# ON_OFF_Controller.net
KiCad netlist of a schematic drawn in Altium Designer
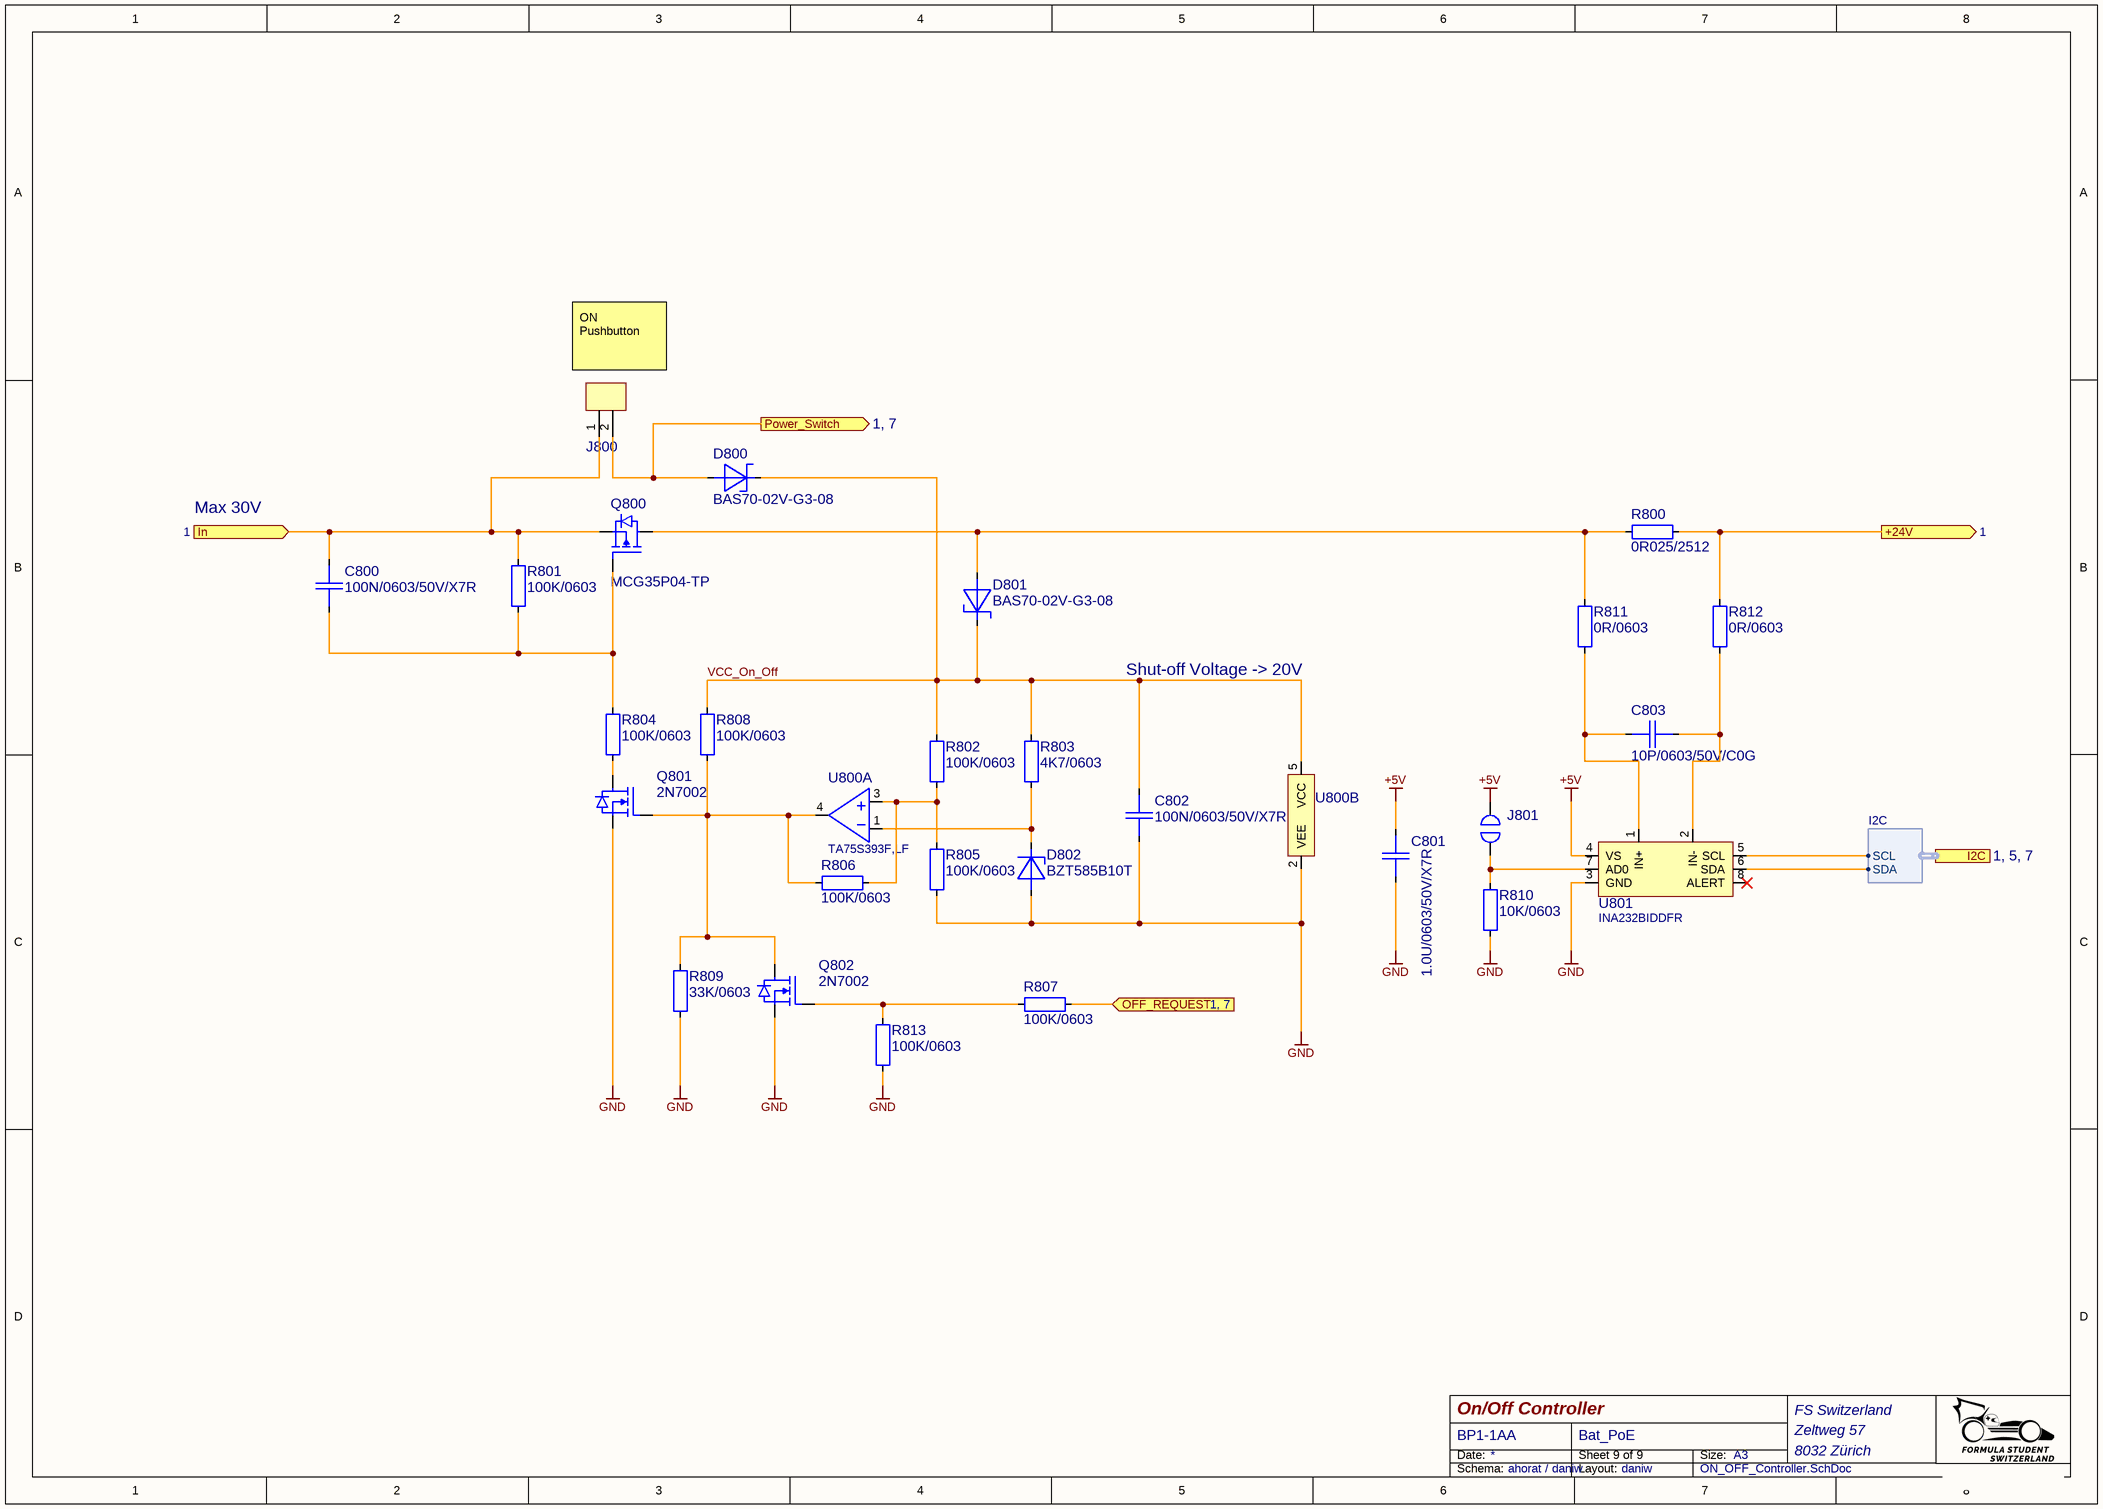
[diagram p0: ON_OFF_Controller.SchDoc]

(export (version "E")
  (design (tool "Eeschema 10.0.6"))
  (components
    (comp (ref "C800")
      (value "100N/0603/50V/X7R")
      (footprint "CAP0603_X7R")
      (description "CAP SM 0603 100nF 50V X7R")
      (fields (field (name "MANUFACTURER") "GENERIC"))
      (libsource (lib "daniw_altium_lib") (part "C"))
    )
    (comp (ref "C801")
      (value "1.0U/0603/50V/X7R")
      (footprint "CAP0603_X7R")
      (description "CAP SM 0603 1.0uF 50V X7R")
      (fields (field (name "MANUFACTURER") "GENERIC"))
      (libsource (lib "daniw_altium_lib") (part "C"))
    )
    (comp (ref "C802")
      (value "100N/0603/50V/X7R")
      (footprint "CAP0603_X7R")
      (description "CAP SM 0603 100nF 50V X7R")
      (fields (field (name "MANUFACTURER") "GENERIC"))
      (libsource (lib "daniw_altium_lib") (part "C"))
    )
    (comp (ref "C803")
      (value "10P/0603/50V/C0G")
      (footprint "CAP0603_C0G")
      (description "CAP SM 0603 10pF 50V C0G")
      (fields (field (name "MANUFACTURER") "GENERIC"))
      (libsource (lib "daniw_altium_lib") (part "C"))
    )
    (comp (ref "D800")
      (value "BAS70-02V-G3-08")
      (footprint "SOD1608X065")
      (description "Small Signal Schottky Diode")
      (fields (field (name "MANUFACTURER") "Vishay"))
      (libsource (lib "daniw_altium_lib") (part "D_Schottky"))
    )
    (comp (ref "D801")
      (value "BAS70-02V-G3-08")
      (footprint "SOD1608X065")
      (description "Small Signal Schottky Diode")
      (fields (field (name "MANUFACTURER") "Vishay"))
      (libsource (lib "daniw_altium_lib") (part "D_Schottky"))
    )
    (comp (ref "D802")
      (value "BZT585B10T")
      (footprint "SOD1608X065")
      (description "DIODE ZENER 10V 350MW SOD523")
      (fields (field (name "MANUFACTURER") "Diodes Incorporated"))
      (libsource (lib "daniw_altium_lib") (part "D_Zener"))
    )
    (comp (ref "J800")
      (value "5600200220")
      (footprint "5600200220")
      (description "DuraClik Wire-to-Board Header, Single Row, Vertical, 2 Circuits, Tin (Sn) Over Nickel, Natural")
      (fields (field (name "PART NUMBER") "DuraClick_1x2_VERT_SMD") (field (name "MANUFACTURER") "Molex"))
      (libsource (lib "daniw_altium_lib") (part "CON2"))
    )
    (comp (ref "J801")
      (value "Solder Jumper 2pin 0.2mm small")
      (footprint "Solder_Jumper_2pin_0.2mm_small")
      (description "Solder jumper with two pins with a spacing of 0.2mm")
      (fields
        (field (name "PART NUMBER") "Solder_Jumper_2pin_0.2mm_small")
        (field (name "MANUFACTURER") "NONE")
      )
      (libsource (lib "daniw_altium_lib") (part "SolderJumper_2"))
    )
    (comp (ref "Q800")
      (value "MCG35P04-TP")
      (footprint "SON065P330X330X075-5-TH245X175")
      (description "40V 35A P-Channel MOSFET")
      (fields (field (name "MANUFACTURER") "Micro Commercial Co"))
      (libsource (lib "daniw_altium_lib") (part "MOSFET P"))
    )
    (comp (ref "Q801")
      (value "2N7002")
      (footprint "SOT2395P280X125-3-SE")
      (description "60V 115mA 1.2Ω@10V,500mA 200mW 2.1V@250uA N Channel SOT-23 MOSFETs")
      (fields (field (name "MANUFACTURER") "GENERIC"))
      (libsource (lib "daniw_altium_lib") (part "MOSFET N_SOT23"))
    )
    (comp (ref "Q802")
      (value "2N7002")
      (footprint "SOT2395P280X125-3-SE")
      (description "60V 115mA 1.2Ω@10V,500mA 200mW 2.1V@250uA N Channel SOT-23 MOSFETs")
      (fields (field (name "MANUFACTURER") "GENERIC"))
      (libsource (lib "daniw_altium_lib") (part "MOSFET N_SOT23"))
    )
    (comp (ref "R800")
      (value "0R025/2512")
      (footprint "R2512-0.65-WW")
      (description "RES SM 2512 0R025")
      (fields (field (name "MANUFACTURER") "GENERIC"))
      (libsource (lib "daniw_altium_lib") (part "R"))
    )
    (comp (ref "R801")
      (value "100K/0603")
      (footprint "R0603-0.40-WW")
      (description "RES SM 0603 100K")
      (fields (field (name "MANUFACTURER") "GENERIC"))
      (libsource (lib "daniw_altium_lib") (part "R"))
    )
    (comp (ref "R802")
      (value "100K/0603")
      (footprint "R0603-0.40-WW")
      (description "RES SM 0603 100K")
      (fields (field (name "MANUFACTURER") "GENERIC"))
      (libsource (lib "daniw_altium_lib") (part "R"))
    )
    (comp (ref "R803")
      (value "4K7/0603")
      (footprint "R0603-0.40-WW")
      (description "RES SM 0603 4K7")
      (fields (field (name "MANUFACTURER") "GENERIC"))
      (libsource (lib "daniw_altium_lib") (part "R"))
    )
    (comp (ref "R804")
      (value "100K/0603")
      (footprint "R0603-0.40-WW")
      (description "RES SM 0603 100K")
      (fields (field (name "MANUFACTURER") "GENERIC"))
      (libsource (lib "daniw_altium_lib") (part "R"))
    )
    (comp (ref "R805")
      (value "100K/0603")
      (footprint "R0603-0.40-WW")
      (description "RES SM 0603 100K")
      (fields (field (name "MANUFACTURER") "GENERIC"))
      (libsource (lib "daniw_altium_lib") (part "R"))
    )
    (comp (ref "R806")
      (value "100K/0603")
      (footprint "R0603-0.40-WW")
      (description "RES SM 0603 100K")
      (fields (field (name "MANUFACTURER") "GENERIC"))
      (libsource (lib "daniw_altium_lib") (part "R"))
    )
    (comp (ref "R807")
      (value "100K/0603")
      (footprint "R0603-0.40-WW")
      (description "RES SM 0603 100K")
      (fields (field (name "MANUFACTURER") "GENERIC"))
      (libsource (lib "daniw_altium_lib") (part "R"))
    )
    (comp (ref "R808")
      (value "100K/0603")
      (footprint "R0603-0.40-WW")
      (description "RES SM 0603 100K")
      (fields (field (name "MANUFACTURER") "GENERIC"))
      (libsource (lib "daniw_altium_lib") (part "R"))
    )
    (comp (ref "R809")
      (value "33K/0603")
      (footprint "R0603-0.40-WW")
      (description "RES SM 0603 33K")
      (fields (field (name "MANUFACTURER") "GENERIC"))
      (libsource (lib "daniw_altium_lib") (part "R"))
    )
    (comp (ref "R810")
      (value "10K/0603")
      (footprint "R0603-0.40-WW")
      (description "RES SM 0603 10K")
      (fields (field (name "MANUFACTURER") "GENERIC"))
      (libsource (lib "daniw_altium_lib") (part "R"))
    )
    (comp (ref "R811")
      (value "0R/0603")
      (footprint "R0603-0.40-WW")
      (description "RES SM 0603 0R")
      (fields (field (name "MANUFACTURER") "GENERIC"))
      (libsource (lib "daniw_altium_lib") (part "R"))
    )
    (comp (ref "R812")
      (value "0R/0603")
      (footprint "R0603-0.40-WW")
      (description "RES SM 0603 0R")
      (fields (field (name "MANUFACTURER") "GENERIC"))
      (libsource (lib "daniw_altium_lib") (part "R"))
    )
    (comp (ref "R813")
      (value "100K/0603")
      (footprint "R0603-0.40-WW")
      (description "RES SM 0603 100K")
      (fields (field (name "MANUFACTURER") "GENERIC"))
      (libsource (lib "daniw_altium_lib") (part "R"))
    )
    (comp (ref "U800")
      (value "TA75S393F,LF")
      (footprint "SOT2395P280X125-5-SW")
      (description "36V Single Voltage Comparator")
      (fields (field (name "MANUFACTURER") "Toshiba Semiconductor and Storage"))
      (libsource (lib "") (part "OPA_SOT23_1"))
    )
    (comp (ref "U801")
      (value "INA232BIDDFR")
      (footprint "SOT065P280X110-8-SE")
      (description "INA232 48-V, 16-Bit, Current, Voltage, and Power Monitor With an I2C Interface")
      (fields (field (name "MANUFACTURER") "Texas Instruments"))
      (libsource (lib "daniw_altium_lib") (part "INA232"))
    )
  )
  (nets
    (net (code "2") (name "+5V") (class "Default")
      (node (ref "C801") (pin "1") (pinfunction "1_1") (pintype "passive"))
      (node (ref "J801") (pin "1") (pinfunction "1_1") (pintype "passive"))
      (node (ref "U801") (pin "4") (pinfunction "VS_4") (pintype "passive"))
    )
    (net (code "3") (name "/+24V") (class "Default")
      (node (ref "R800") (pin "2") (pinfunction "2_2") (pintype "passive"))
      (node (ref "R812") (pin "1") (pinfunction "1_1") (pintype "passive"))
    )
    (net (code "4") (name "/In") (class "Default")
      (node (ref "C800") (pin "1") (pinfunction "1_1") (pintype "passive"))
      (node (ref "J800") (pin "1") (pintype "passive"))
      (node (ref "Q800") (pin "S") (pinfunction "SOURCE_S") (pintype "passive"))
      (node (ref "R801") (pin "1") (pinfunction "1_1") (pintype "passive"))
    )
    (net (code "5") (name "/OFF_REQUEST") (class "Default")
      (node (ref "R807") (pin "1") (pinfunction "1_1") (pintype "passive"))
    )
    (net (code "6") (name "/Power_Switch") (class "Default")
      (node (ref "D800") (pin "2") (pinfunction "2_2") (pintype "passive"))
      (node (ref "J800") (pin "2") (pintype "passive"))
    )
    (net (code "7") (name "/SCL") (class "Default")
      (node (ref "U801") (pin "5") (pinfunction "SCL_5") (pintype "passive"))
    )
    (net (code "8") (name "/SDA") (class "Default")
      (node (ref "U801") (pin "6") (pinfunction "SDA_6") (pintype "passive"))
    )
    (net (code "9") (name "/VCC_On_Off") (class "Default")
      (node (ref "C802") (pin "1") (pinfunction "1_1") (pintype "passive"))
      (node (ref "D800") (pin "1") (pinfunction "1_1") (pintype "passive"))
      (node (ref "D801") (pin "1") (pinfunction "1_1") (pintype "passive"))
      (node (ref "R802") (pin "1") (pinfunction "1_1") (pintype "passive"))
      (node (ref "R803") (pin "1") (pinfunction "1_1") (pintype "passive"))
      (node (ref "R808") (pin "1") (pinfunction "1_1") (pintype "passive"))
      (node (ref "U800") (pin "5") (pinfunction "VCC_5") (pintype "passive"))
    )
    (net (code "11") (name "GND") (class "Default")
      (node (ref "C801") (pin "2") (pinfunction "2_2") (pintype "passive"))
      (node (ref "C802") (pin "2") (pinfunction "2_2") (pintype "passive"))
      (node (ref "D802") (pin "2") (pinfunction "2_2") (pintype "passive"))
      (node (ref "Q801") (pin "2") (pinfunction "SOURCE_2") (pintype "passive"))
      (node (ref "Q802") (pin "2") (pinfunction "SOURCE_2") (pintype "passive"))
      (node (ref "R805") (pin "2") (pinfunction "2_2") (pintype "passive"))
      (node (ref "R809") (pin "2") (pinfunction "2_2") (pintype "passive"))
      (node (ref "R810") (pin "2") (pinfunction "2_2") (pintype "passive"))
      (node (ref "R813") (pin "2") (pinfunction "2_2") (pintype "passive"))
      (node (ref "U800") (pin "2") (pinfunction "VEE_2") (pintype "passive"))
      (node (ref "U801") (pin "3") (pinfunction "GND_3") (pintype "passive"))
    )
    (net (code "12") (name "Net-(Q800-DRAIN)") (class "Default")
      (node (ref "D801") (pin "2") (pinfunction "2_2") (pintype "passive"))
      (node (ref "Q800") (pin "D") (pinfunction "DRAIN_D") (pintype "passive"))
      (node (ref "R800") (pin "1") (pinfunction "1_1") (pintype "passive"))
      (node (ref "R811") (pin "1") (pinfunction "1_1") (pintype "passive"))
    )
    (net (code "13") (name "Net-(Q800-GATE)") (class "Default")
      (node (ref "C800") (pin "2") (pinfunction "2_2") (pintype "passive"))
      (node (ref "Q800") (pin "G") (pinfunction "GATE_G") (pintype "passive"))
      (node (ref "R801") (pin "2") (pinfunction "2_2") (pintype "passive"))
      (node (ref "R804") (pin "1") (pinfunction "1_1") (pintype "passive"))
    )
    (net (code "14") (name "Net-(Q801-DRAIN)") (class "Default")
      (node (ref "Q801") (pin "3") (pinfunction "DRAIN_3") (pintype "passive"))
      (node (ref "R804") (pin "2") (pinfunction "2_2") (pintype "passive"))
    )
    (net (code "15") (name "Net-(Q801-GATE)") (class "Default")
      (node (ref "Q801") (pin "1") (pinfunction "GATE_1") (pintype "passive"))
      (node (ref "Q802") (pin "3") (pinfunction "DRAIN_3") (pintype "passive"))
      (node (ref "R806") (pin "2") (pinfunction "2_2") (pintype "passive"))
      (node (ref "R808") (pin "2") (pinfunction "2_2") (pintype "passive"))
      (node (ref "R809") (pin "1") (pinfunction "1_1") (pintype "passive"))
      (node (ref "U800") (pin "4") (pinfunction "OUT_4") (pintype "passive"))
    )
    (net (code "16") (name "Net-(Q802-GATE)") (class "Default")
      (node (ref "Q802") (pin "1") (pinfunction "GATE_1") (pintype "passive"))
      (node (ref "R807") (pin "2") (pinfunction "2_2") (pintype "passive"))
      (node (ref "R813") (pin "1") (pinfunction "1_1") (pintype "passive"))
    )
    (net (code "17") (name "Net-(U800A-IN+)") (class "Default")
      (node (ref "R802") (pin "2") (pinfunction "2_2") (pintype "passive"))
      (node (ref "R805") (pin "1") (pinfunction "1_1") (pintype "passive"))
      (node (ref "R806") (pin "1") (pinfunction "1_1") (pintype "passive"))
      (node (ref "U800") (pin "3") (pinfunction "IN+_3") (pintype "passive"))
    )
    (net (code "18") (name "Net-(U800A-IN-)") (class "Default")
      (node (ref "D802") (pin "1") (pinfunction "1_1") (pintype "passive"))
      (node (ref "R803") (pin "2") (pinfunction "2_2") (pintype "passive"))
      (node (ref "U800") (pin "1") (pinfunction "IN-_1") (pintype "passive"))
    )
    (net (code "19") (name "Net-(U801-AD0)") (class "Default")
      (node (ref "J801") (pin "2") (pinfunction "2_2") (pintype "passive"))
      (node (ref "R810") (pin "1") (pinfunction "1_1") (pintype "passive"))
      (node (ref "U801") (pin "7") (pinfunction "AD0_7") (pintype "passive"))
    )
    (net (code "20") (name "Net-(U801-IN+)") (class "Default")
      (node (ref "C803") (pin "2") (pinfunction "2_2") (pintype "passive"))
      (node (ref "R811") (pin "2") (pinfunction "2_2") (pintype "passive"))
      (node (ref "U801") (pin "1") (pinfunction "IN+_1") (pintype "passive"))
    )
    (net (code "21") (name "Net-(U801-IN-)") (class "Default")
      (node (ref "C803") (pin "1") (pinfunction "1_1") (pintype "passive"))
      (node (ref "R812") (pin "2") (pinfunction "2_2") (pintype "passive"))
      (node (ref "U801") (pin "2") (pinfunction "IN-_2") (pintype "passive"))
    )
    (net (code "22") (name "unconnected-(U801-ALERT-Pad8)") (class "Default")
      (node (ref "U801") (pin "8") (pinfunction "ALERT_8") (pintype "passive+no_connect"))
    )
  )
)
